# ArduinoClock.net
KiCad netlist of a schematic drawn in EAGLE
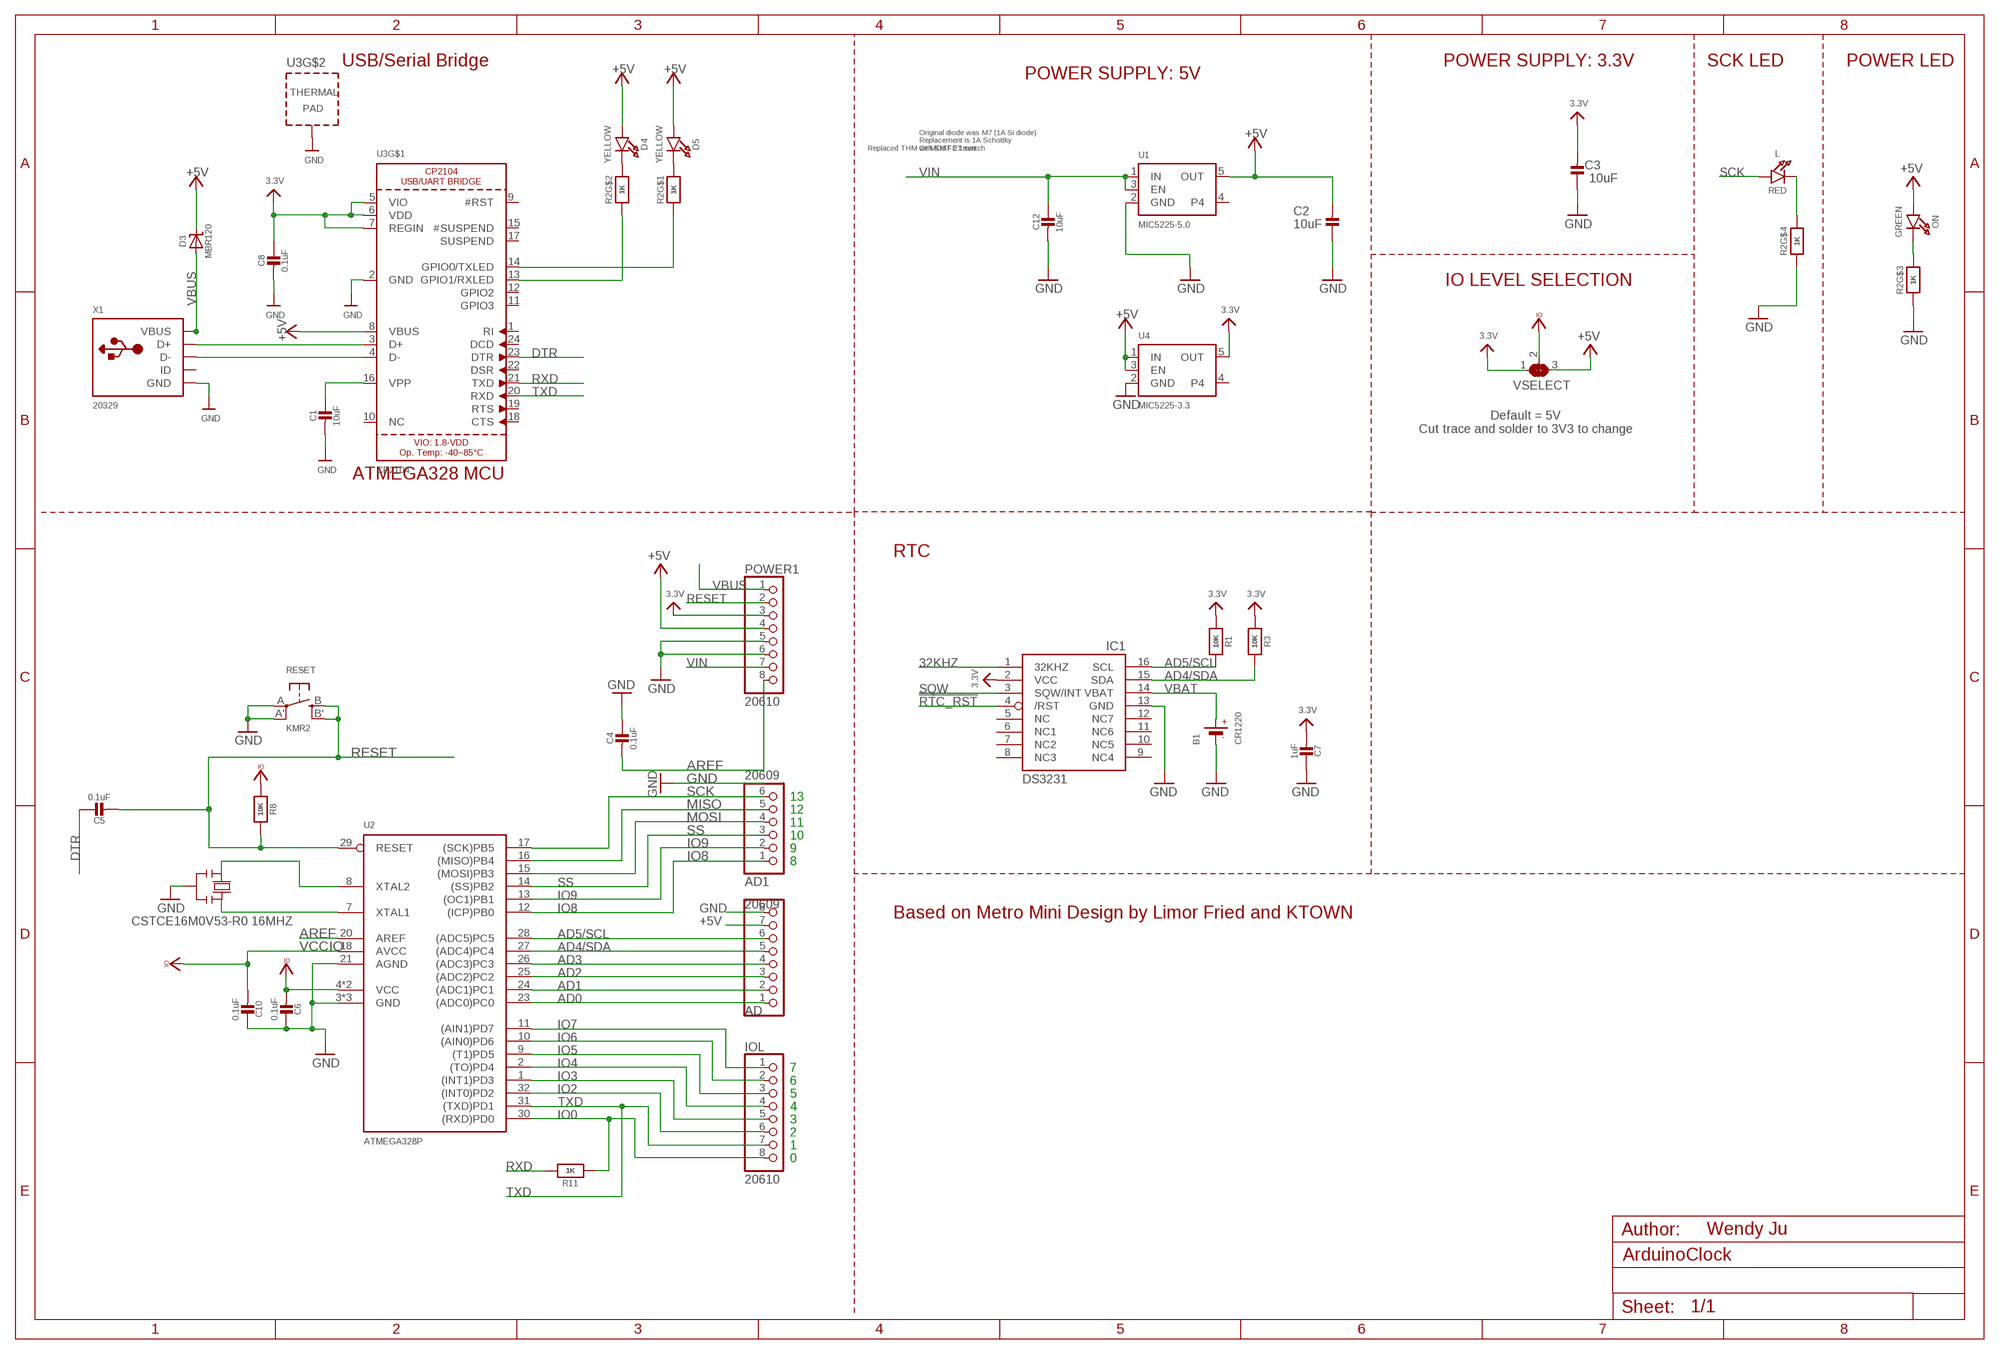
[diagram p0: schematic, sheet 1]

(export (version "E")
  (design (tool "Eeschema 10.0.6"))
  (components
    (comp (ref "AD")
      (value "20609")
      (footprint "eagle-import:1X08_ROUND")
      (libsource (lib "eagle-import") (part "HEADER-1X8ROUND"))
    )
    (comp (ref "AD1")
      (value "20609")
      (footprint "eagle-import:1X06_ROUND")
      (libsource (lib "eagle-import") (part "HEADER-1X6ROUND"))
    )
    (comp (ref "B1")
      (value "CR1220")
      (footprint "eagle-import:CR1220")
      (libsource (lib "eagle-import") (part "BATTERYCR1220_SMT"))
    )
    (comp (ref "C1")
      (value "10uF")
      (footprint "eagle-import:0805-NO")
      (libsource (lib "eagle-import") (part "CAP_CERAMIC0805-NOOUTLINE"))
    )
    (comp (ref "C2")
      (value "10uF")
      (footprint "eagle-import:0805-NO")
      (libsource (lib "eagle-import") (part "CAP_CERAMIC0805-NOOUTLINE"))
    )
    (comp (ref "C3")
      (value "10uF")
      (footprint "eagle-import:0805-NO")
      (libsource (lib "eagle-import") (part "CAP_CERAMIC0805-NOOUTLINE"))
    )
    (comp (ref "C4")
      (value "0.1uF")
      (footprint "eagle-import:0805-NO")
      (libsource (lib "eagle-import") (part "CAP_CERAMIC0805-NOOUTLINE"))
    )
    (comp (ref "C5")
      (value "0.1uF")
      (footprint "eagle-import:_0805MP")
      (libsource (lib "eagle-import") (part "CAP_CERAMIC_0805MP"))
    )
    (comp (ref "C6")
      (value "0.1uF")
      (footprint "eagle-import:0805-NO")
      (libsource (lib "eagle-import") (part "CAP_CERAMIC0805-NOOUTLINE"))
    )
    (comp (ref "C7")
      (value "1uF")
      (footprint "eagle-import:0805-NO")
      (libsource (lib "eagle-import") (part "CAP_CERAMIC0805-NOOUTLINE"))
    )
    (comp (ref "C8")
      (value "0.1uF")
      (footprint "eagle-import:0805-NO")
      (libsource (lib "eagle-import") (part "CAP_CERAMIC0805-NOOUTLINE"))
    )
    (comp (ref "C10")
      (value "0.1uF")
      (footprint "eagle-import:0805-NO")
      (libsource (lib "eagle-import") (part "CAP_CERAMIC0805-NOOUTLINE"))
    )
    (comp (ref "C12")
      (value "10uF")
      (footprint "eagle-import:0805-NO")
      (libsource (lib "eagle-import") (part "CAP_CERAMIC0805-NOOUTLINE"))
    )
    (comp (ref "D3")
      (value "MBR120")
      (footprint "eagle-import:SOD-123")
      (libsource (lib "eagle-import") (part "DIODE-SCHOTTKYSOD-123"))
    )
    (comp (ref "D4")
      (value "YELLOW")
      (footprint "eagle-import:CHIPLED_0805_NOOUTLINE")
      (libsource (lib "eagle-import") (part "LED0805_NOOUTLINE"))
    )
    (comp (ref "D5")
      (value "YELLOW")
      (footprint "eagle-import:CHIPLED_0805_NOOUTLINE")
      (libsource (lib "eagle-import") (part "LED0805_NOOUTLINE"))
    )
    (comp (ref "IC1")
      (value "DS3231/SO")
      (footprint "eagle-import:SO16W")
      (libsource (lib "eagle-import") (part "DS3231/SO"))
    )
    (comp (ref "IOL")
      (value "20610")
      (footprint "eagle-import:1X08_ROUND")
      (libsource (lib "eagle-import") (part "HEADER-1X8ROUND"))
    )
    (comp (ref "L")
      (value "RED")
      (footprint "eagle-import:CHIPLED_0805_NOOUTLINE")
      (libsource (lib "eagle-import") (part "LED0805_NOOUTLINE"))
    )
    (comp (ref "ON")
      (value "GREEN")
      (footprint "eagle-import:CHIPLED_0805_NOOUTLINE")
      (libsource (lib "eagle-import") (part "LED0805_NOOUTLINE"))
    )
    (comp (ref "POWER1")
      (value "20610")
      (footprint "eagle-import:1X08_ROUND_70")
      (libsource (lib "eagle-import") (part "HEADER-1X870MIL"))
    )
    (comp (ref "R1")
      (value "10K")
      (footprint "eagle-import:0805-NO")
      (libsource (lib "eagle-import") (part "RESISTOR0805_NOOUTLINE"))
    )
    (comp (ref "R2")
      (value "1K")
      (footprint "eagle-import:RESPACK_4X0603")
      (libsource (lib "eagle-import") (part "RESISTOR_4PACK"))
    )
    (comp (ref "R3")
      (value "10K")
      (footprint "eagle-import:0805-NO")
      (libsource (lib "eagle-import") (part "RESISTOR0805_NOOUTLINE"))
    )
    (comp (ref "R8")
      (value "10K")
      (footprint "eagle-import:0805-NO")
      (libsource (lib "eagle-import") (part "RESISTOR0805_NOOUTLINE"))
    )
    (comp (ref "R11")
      (value "1K")
      (footprint "eagle-import:0805-NO")
      (libsource (lib "eagle-import") (part "RESISTOR0805_NOOUTLINE"))
    )
    (comp (ref "RESET")
      (value "KMR2")
      (footprint "eagle-import:BTN_KMR2_4.6X2.8")
      (libsource (lib "eagle-import") (part "SWITCH_TACT_SMT4.6X2.8"))
    )
    (comp (ref "U1")
      (value "MIC5225-5.0")
      (footprint "eagle-import:SOT23-5")
      (libsource (lib "eagle-import") (part "VREG_SOT23-5"))
    )
    (comp (ref "U2")
      (value "ATMEGA328P")
      (footprint "eagle-import:MLF32-TH")
      (libsource (lib "eagle-import") (part "ATMEGA328P"))
    )
    (comp (ref "U3")
      (value "CP2104")
      (footprint "eagle-import:QFN24_4MM_SMSC")
      (libsource (lib "eagle-import") (part "CP2104"))
    )
    (comp (ref "U4")
      (value "MIC5225-3.3")
      (footprint "eagle-import:SOT23-5")
      (libsource (lib "eagle-import") (part "VREG_SOT23-5"))
    )
    (comp (ref "VSELECT")
      (value "SOLDERJUMPER_2WAY")
      (footprint "eagle-import:SOLDERJUMPER_2WAY_OPEN_NOPASTE")
      (libsource (lib "eagle-import") (part "SOLDERJUMPER_2WAY"))
    )
    (comp (ref "X1")
      (value "20329")
      (footprint "eagle-import:4UCONN_20329_V2")
      (libsource (lib "eagle-import") (part "USB_MICRO_20329_V2"))
    )
    (comp (ref "Y2")
      (value "CSTCE16M0V53-R0 16MHZ")
      (footprint "eagle-import:RESONATOR")
      (libsource (lib "eagle-import") (part "RESONATORMU"))
    )
  )
  (nets
    (net (code "1") (name "+5V") (class "Default")
      (node (ref "AD") (pin "7") (pinfunction "7_7") (pintype "passive"))
      (node (ref "C2") (pin "2") (pinfunction "2_2") (pintype "passive"))
      (node (ref "D3") (pin "C") (pinfunction "C_C") (pintype "passive"))
      (node (ref "D4") (pin "A") (pinfunction "A_A") (pintype "passive"))
      (node (ref "D5") (pin "A") (pinfunction "A_A") (pintype "passive"))
      (node (ref "ON") (pin "A") (pinfunction "A_A") (pintype "passive"))
      (node (ref "POWER1") (pin "4") (pinfunction "4_4") (pintype "passive"))
      (node (ref "U1") (pin "5") (pinfunction "OUT_5") (pintype "power_in"))
      (node (ref "U3") (pin "8") (pinfunction "VBUS_8") (pintype "power_in"))
      (node (ref "U4") (pin "1") (pinfunction "IN_1") (pintype "power_in"))
      (node (ref "U4") (pin "3") (pinfunction "EN_3") (pintype "input"))
      (node (ref "VSELECT") (pin "3") (pinfunction "3_3") (pintype "passive"))
    )
    (net (code "2") (name "/32KHZ") (class "Default")
      (node (ref "IC1") (pin "1") (pinfunction "32KHZ_1") (pintype "output"))
    )
    (net (code "3") (name "/AD0") (class "Default")
      (node (ref "AD") (pin "1") (pinfunction "1_1") (pintype "passive"))
      (node (ref "U2") (pin "23") (pinfunction "(ADC0)PC0_23") (pintype "bidirectional"))
    )
    (net (code "4") (name "/AD1") (class "Default")
      (node (ref "AD") (pin "2") (pinfunction "2_2") (pintype "passive"))
      (node (ref "U2") (pin "24") (pinfunction "(ADC1)PC1_24") (pintype "bidirectional"))
    )
    (net (code "5") (name "/AD2") (class "Default")
      (node (ref "AD") (pin "3") (pinfunction "3_3") (pintype "passive"))
      (node (ref "U2") (pin "25") (pinfunction "(ADC2)PC2_25") (pintype "bidirectional"))
    )
    (net (code "6") (name "/AD3") (class "Default")
      (node (ref "AD") (pin "4") (pinfunction "4_4") (pintype "passive"))
      (node (ref "U2") (pin "26") (pinfunction "(ADC3)PC3_26") (pintype "bidirectional"))
    )
    (net (code "7") (name "/AD4{slash}SDA") (class "Default")
      (node (ref "AD") (pin "5") (pinfunction "5_5") (pintype "passive"))
      (node (ref "IC1") (pin "15") (pinfunction "SDA_15") (pintype "bidirectional"))
      (node (ref "R3") (pin "2") (pinfunction "2_2") (pintype "passive"))
      (node (ref "U2") (pin "27") (pinfunction "(ADC4)PC4_27") (pintype "bidirectional"))
    )
    (net (code "8") (name "/AD5{slash}SCL") (class "Default")
      (node (ref "AD") (pin "6") (pinfunction "6_6") (pintype "passive"))
      (node (ref "IC1") (pin "16") (pinfunction "SCL_16") (pintype "bidirectional"))
      (node (ref "R1") (pin "2") (pinfunction "2_2") (pintype "passive"))
      (node (ref "U2") (pin "28") (pinfunction "(ADC5)PC5_28") (pintype "bidirectional"))
    )
    (net (code "9") (name "/AREF") (class "Default")
      (node (ref "C4") (pin "2") (pinfunction "2_2") (pintype "passive"))
      (node (ref "POWER1") (pin "8") (pinfunction "8_8") (pintype "passive"))
      (node (ref "U2") (pin "20") (pinfunction "AREF_20") (pintype "power_in"))
    )
    (net (code "10") (name "/DTR") (class "Default")
      (node (ref "C5") (pin "1") (pinfunction "1_1") (pintype "passive"))
      (node (ref "U3") (pin "23") (pinfunction "DTR_23") (pintype "output"))
    )
    (net (code "11") (name "/IO0") (class "Default")
      (node (ref "IOL") (pin "8") (pinfunction "8_8") (pintype "passive"))
      (node (ref "R11") (pin "1") (pinfunction "1_1") (pintype "passive"))
      (node (ref "U2") (pin "30") (pinfunction "(RXD)PD0_30") (pintype "bidirectional"))
    )
    (net (code "12") (name "/IO2") (class "Default")
      (node (ref "IOL") (pin "6") (pinfunction "6_6") (pintype "passive"))
      (node (ref "U2") (pin "32") (pinfunction "(INT0)PD2_32") (pintype "bidirectional"))
    )
    (net (code "13") (name "/IO3") (class "Default")
      (node (ref "IOL") (pin "5") (pinfunction "5_5") (pintype "passive"))
      (node (ref "U2") (pin "1") (pinfunction "(INT1)PD3_1") (pintype "bidirectional"))
    )
    (net (code "14") (name "/IO4") (class "Default")
      (node (ref "IOL") (pin "4") (pinfunction "4_4") (pintype "passive"))
      (node (ref "U2") (pin "2") (pinfunction "(TO)PD4_2") (pintype "bidirectional"))
    )
    (net (code "15") (name "/IO5") (class "Default")
      (node (ref "IOL") (pin "3") (pinfunction "3_3") (pintype "passive"))
      (node (ref "U2") (pin "9") (pinfunction "(T1)PD5_9") (pintype "bidirectional"))
    )
    (net (code "16") (name "/IO6") (class "Default")
      (node (ref "IOL") (pin "2") (pinfunction "2_2") (pintype "passive"))
      (node (ref "U2") (pin "10") (pinfunction "(AIN0)PD6_10") (pintype "bidirectional"))
    )
    (net (code "17") (name "/IO7") (class "Default")
      (node (ref "IOL") (pin "1") (pinfunction "1_1") (pintype "passive"))
      (node (ref "U2") (pin "11") (pinfunction "(AIN1)PD7_11") (pintype "bidirectional"))
    )
    (net (code "18") (name "/IO8") (class "Default")
      (node (ref "AD1") (pin "1") (pinfunction "1_1") (pintype "passive"))
      (node (ref "U2") (pin "12") (pinfunction "(ICP)PB0_12") (pintype "bidirectional"))
    )
    (net (code "19") (name "/IO9") (class "Default")
      (node (ref "AD1") (pin "2") (pinfunction "2_2") (pintype "passive"))
      (node (ref "U2") (pin "13") (pinfunction "(OC1)PB1_13") (pintype "bidirectional"))
    )
    (net (code "20") (name "/MISO") (class "Default")
      (node (ref "AD1") (pin "5") (pinfunction "5_5") (pintype "passive"))
      (node (ref "U2") (pin "16") (pinfunction "(MISO)PB4_16") (pintype "bidirectional"))
    )
    (net (code "21") (name "/MOSI") (class "Default")
      (node (ref "AD1") (pin "4") (pinfunction "4_4") (pintype "passive"))
      (node (ref "U2") (pin "15") (pinfunction "(MOSI)PB3_15") (pintype "bidirectional"))
    )
    (net (code "22") (name "/RESET") (class "Default")
      (node (ref "C5") (pin "2") (pinfunction "2_2") (pintype "passive"))
      (node (ref "POWER1") (pin "2") (pinfunction "2_2") (pintype "passive"))
      (node (ref "R8") (pin "1") (pinfunction "1_1") (pintype "passive"))
      (node (ref "RESET") (pin "B") (pinfunction "S_B") (pintype "passive"))
      (node (ref "RESET") (pin "B'") (pinfunction "S1_B'") (pintype "passive"))
      (node (ref "U2") (pin "29") (pinfunction "RESET_29") (pintype "bidirectional"))
    )
    (net (code "23") (name "/RXD") (class "Default")
      (node (ref "R11") (pin "2") (pinfunction "2_2") (pintype "passive"))
      (node (ref "U3") (pin "21") (pinfunction "TXD_21") (pintype "output"))
    )
    (net (code "24") (name "/SCK") (class "Default")
      (node (ref "AD1") (pin "6") (pinfunction "6_6") (pintype "passive"))
      (node (ref "L") (pin "A") (pinfunction "A_A") (pintype "passive"))
      (node (ref "U2") (pin "17") (pinfunction "(SCK)PB5_17") (pintype "bidirectional"))
    )
    (net (code "25") (name "/SQW") (class "Default")
      (node (ref "IC1") (pin "3") (pinfunction "SQW/INT_3") (pintype "output"))
    )
    (net (code "26") (name "/SS") (class "Default")
      (node (ref "AD1") (pin "3") (pinfunction "3_3") (pintype "passive"))
      (node (ref "U2") (pin "14") (pinfunction "(SS)PB2_14") (pintype "bidirectional"))
    )
    (net (code "27") (name "/TXD") (class "Default")
      (node (ref "IOL") (pin "7") (pinfunction "7_7") (pintype "passive"))
      (node (ref "U2") (pin "31") (pinfunction "(TXD)PD1_31") (pintype "bidirectional"))
      (node (ref "U3") (pin "20") (pinfunction "RXD_20") (pintype "input"))
    )
    (net (code "28") (name "/VBAT") (class "Default")
      (node (ref "B1") (pin "+$1") (pinfunction "+_+$1") (pintype "passive"))
      (node (ref "IC1") (pin "14") (pinfunction "VBAT_14") (pintype "power_in"))
    )
    (net (code "29") (name "/VBUS") (class "Default")
      (node (ref "D3") (pin "A") (pinfunction "A_A") (pintype "passive"))
      (node (ref "POWER1") (pin "1") (pinfunction "1_1") (pintype "passive"))
      (node (ref "X1") (pin "VBUS") (pinfunction "VBUS_VBUS") (pintype "power_in"))
    )
    (net (code "30") (name "/VIN") (class "Default")
      (node (ref "C12") (pin "1") (pinfunction "1_1") (pintype "passive"))
      (node (ref "POWER1") (pin "7") (pinfunction "7_7") (pintype "passive"))
      (node (ref "U1") (pin "1") (pinfunction "IN_1") (pintype "power_in"))
      (node (ref "U1") (pin "3") (pinfunction "EN_3") (pintype "input"))
    )
    (net (code "31") (name "/~{RTC_RST}") (class "Default")
      (node (ref "IC1") (pin "4") (pinfunction "/RST_4") (pintype "passive"))
    )
    (net (code "32") (name "3.3V") (class "Default")
      (node (ref "C3") (pin "2") (pinfunction "2_2") (pintype "passive"))
      (node (ref "C7") (pin "2") (pinfunction "2_2") (pintype "passive"))
      (node (ref "C8") (pin "1") (pinfunction "1_1") (pintype "passive"))
      (node (ref "IC1") (pin "2") (pinfunction "VCC_2") (pintype "power_in"))
      (node (ref "POWER1") (pin "3") (pinfunction "3_3") (pintype "passive"))
      (node (ref "R1") (pin "1") (pinfunction "1_1") (pintype "passive"))
      (node (ref "R3") (pin "1") (pinfunction "1_1") (pintype "passive"))
      (node (ref "U3") (pin "5") (pinfunction "VIO_5") (pintype "power_in"))
      (node (ref "U3") (pin "6") (pinfunction "VDD_6") (pintype "power_in"))
      (node (ref "U3") (pin "7") (pinfunction "REGIN_7") (pintype "power_in"))
      (node (ref "U4") (pin "5") (pinfunction "OUT_5") (pintype "power_in"))
      (node (ref "VSELECT") (pin "1") (pinfunction "1_1") (pintype "passive"))
    )
    (net (code "33") (name "GND") (class "Default")
      (node (ref "AD") (pin "8") (pinfunction "8_8") (pintype "passive"))
      (node (ref "B1") (pin "-") (pinfunction "-_-") (pintype "passive"))
      (node (ref "C1") (pin "2") (pinfunction "2_2") (pintype "passive"))
      (node (ref "C10") (pin "1") (pinfunction "1_1") (pintype "passive"))
      (node (ref "C12") (pin "2") (pinfunction "2_2") (pintype "passive"))
      (node (ref "C2") (pin "1") (pinfunction "1_1") (pintype "passive"))
      (node (ref "C3") (pin "1") (pinfunction "1_1") (pintype "passive"))
      (node (ref "C4") (pin "1") (pinfunction "1_1") (pintype "passive"))
      (node (ref "C6") (pin "1") (pinfunction "1_1") (pintype "passive"))
      (node (ref "C7") (pin "1") (pinfunction "1_1") (pintype "passive"))
      (node (ref "C8") (pin "2") (pinfunction "2_2") (pintype "passive"))
      (node (ref "IC1") (pin "13") (pinfunction "GND_13") (pintype "power_in"))
      (node (ref "POWER1") (pin "5") (pinfunction "5_5") (pintype "passive"))
      (node (ref "POWER1") (pin "6") (pinfunction "6_6") (pintype "passive"))
      (node (ref "R2") (pin "3") (pinfunction "1_3") (pintype "passive"))
      (node (ref "R2") (pin "4") (pinfunction "1_4") (pintype "passive"))
      (node (ref "RESET") (pin "A") (pinfunction "P_A") (pintype "passive"))
      (node (ref "RESET") (pin "A'") (pinfunction "P1_A'") (pintype "passive"))
      (node (ref "U1") (pin "2") (pinfunction "GND_2") (pintype "power_in"))
      (node (ref "U2") (pin "21") (pinfunction "AGND_21") (pintype "power_in"))
      (node (ref "U2") (pin "3") (pinfunction "GND_3") (pintype "power_in"))
      (node (ref "U2") (pin "5") (pinfunction "GND_5") (pintype "power_in"))
      (node (ref "U2") (pin "TH") (pinfunction "GND_TH") (pintype "power_in"))
      (node (ref "U3") (pin "2") (pinfunction "GND_2") (pintype "power_in"))
      (node (ref "U3") (pin "THERM") (pinfunction "TP_THERM") (pintype "power_in"))
      (node (ref "U4") (pin "2") (pinfunction "GND_2") (pintype "power_in"))
      (node (ref "X1") (pin "BASE@1") (pinfunction "GND_BASE@1") (pintype "power_in"))
      (node (ref "X1") (pin "BASE@2") (pinfunction "GND_BASE@2") (pintype "power_in"))
      (node (ref "X1") (pin "GND") (pinfunction "GND_GND") (pintype "power_in"))
      (node (ref "X1") (pin "SPRT@1") (pinfunction "GND_SPRT@1") (pintype "power_in"))
      (node (ref "X1") (pin "SPRT@2") (pinfunction "GND_SPRT@2") (pintype "power_in"))
      (node (ref "X1") (pin "SPRT@3") (pinfunction "GND_SPRT@3") (pintype "power_in"))
      (node (ref "X1") (pin "SPRT@4") (pinfunction "GND_SPRT@4") (pintype "power_in"))
      (node (ref "Y2") (pin "2") (pinfunction "2_2") (pintype "passive"))
    )
    (net (code "34") (name "Net-(R2A-2)") (class "Default")
      (node (ref "D5") (pin "C") (pinfunction "C_C") (pintype "passive"))
      (node (ref "R2") (pin "8") (pinfunction "2_8") (pintype "passive"))
    )
    (net (code "35") (name "Net-(R2B-1)") (class "Default")
      (node (ref "R2") (pin "2") (pinfunction "1_2") (pintype "passive"))
      (node (ref "U3") (pin "13") (pinfunction "GPIO1/RXLED_13") (pintype "bidirectional"))
    )
    (net (code "36") (name "Net-(R2B-2)") (class "Default")
      (node (ref "D4") (pin "C") (pinfunction "C_C") (pintype "passive"))
      (node (ref "R2") (pin "7") (pinfunction "2_7") (pintype "passive"))
    )
    (net (code "37") (name "Net-(R2C-2)") (class "Default")
      (node (ref "ON") (pin "C") (pinfunction "C_C") (pintype "passive"))
      (node (ref "R2") (pin "6") (pinfunction "2_6") (pintype "passive"))
    )
    (net (code "38") (name "Net-(R2D-2)") (class "Default")
      (node (ref "L") (pin "C") (pinfunction "C_C") (pintype "passive"))
      (node (ref "R2") (pin "5") (pinfunction "2_5") (pintype "passive"))
    )
    (net (code "39") (name "Net-(U2-XTAL1)") (class "Default")
      (node (ref "U2") (pin "7") (pinfunction "XTAL1_7") (pintype "bidirectional"))
      (node (ref "Y2") (pin "3") (pinfunction "3_3") (pintype "passive"))
    )
    (net (code "40") (name "Net-(U2-XTAL2)") (class "Default")
      (node (ref "U2") (pin "8") (pinfunction "XTAL2_8") (pintype "bidirectional"))
      (node (ref "Y2") (pin "1") (pinfunction "1_1") (pintype "passive"))
    )
    (net (code "41") (name "Net-(U3A-D+)") (class "Default")
      (node (ref "U3") (pin "3") (pinfunction "D+_3") (pintype "bidirectional"))
      (node (ref "X1") (pin "D+") (pinfunction "D+_D+") (pintype "bidirectional"))
    )
    (net (code "42") (name "Net-(U3A-D-)") (class "Default")
      (node (ref "U3") (pin "4") (pinfunction "D-_4") (pintype "bidirectional"))
      (node (ref "X1") (pin "D-") (pinfunction "D-_D-") (pintype "bidirectional"))
    )
    (net (code "43") (name "Net-(U3A-GPIO0{slash}TXLED)") (class "Default")
      (node (ref "R2") (pin "1") (pinfunction "1_1") (pintype "passive"))
      (node (ref "U3") (pin "14") (pinfunction "GPIO0/TXLED_14") (pintype "bidirectional"))
    )
    (net (code "44") (name "Net-(U3A-VPP)") (class "Default")
      (node (ref "C1") (pin "1") (pinfunction "1_1") (pintype "passive"))
      (node (ref "U3") (pin "16") (pinfunction "VPP_16") (pintype "bidirectional"))
    )
    (net (code "45") (name "VCCIO") (class "Default")
      (node (ref "C10") (pin "2") (pinfunction "2_2") (pintype "passive"))
      (node (ref "C6") (pin "2") (pinfunction "2_2") (pintype "passive"))
      (node (ref "R8") (pin "2") (pinfunction "2_2") (pintype "passive"))
      (node (ref "U2") (pin "18") (pinfunction "AVCC_18") (pintype "power_in"))
      (node (ref "U2") (pin "4") (pinfunction "VCC_4") (pintype "power_in"))
      (node (ref "U2") (pin "6") (pinfunction "VCC_6") (pintype "power_in"))
      (node (ref "VSELECT") (pin "2") (pinfunction "2_2") (pintype "passive"))
    )
    (net (code "46") (name "unconnected-(IC1-NC-Pad5)") (class "Default")
      (node (ref "IC1") (pin "5") (pinfunction "NC_5") (pintype "no_connect"))
    )
    (net (code "47") (name "unconnected-(IC1-NC1-Pad6)") (class "Default")
      (node (ref "IC1") (pin "6") (pinfunction "NC1_6") (pintype "no_connect"))
    )
    (net (code "48") (name "unconnected-(IC1-NC2-Pad7)") (class "Default")
      (node (ref "IC1") (pin "7") (pinfunction "NC2_7") (pintype "no_connect"))
    )
    (net (code "49") (name "unconnected-(IC1-NC3-Pad8)") (class "Default")
      (node (ref "IC1") (pin "8") (pinfunction "NC3_8") (pintype "no_connect"))
    )
    (net (code "50") (name "unconnected-(IC1-NC4-Pad9)") (class "Default")
      (node (ref "IC1") (pin "9") (pinfunction "NC4_9") (pintype "no_connect"))
    )
    (net (code "51") (name "unconnected-(IC1-NC5-Pad10)") (class "Default")
      (node (ref "IC1") (pin "10") (pinfunction "NC5_10") (pintype "no_connect"))
    )
    (net (code "52") (name "unconnected-(IC1-NC6-Pad11)") (class "Default")
      (node (ref "IC1") (pin "11") (pinfunction "NC6_11") (pintype "no_connect"))
    )
    (net (code "53") (name "unconnected-(IC1-NC7-Pad12)") (class "Default")
      (node (ref "IC1") (pin "12") (pinfunction "NC7_12") (pintype "no_connect"))
    )
    (net (code "54") (name "unconnected-(U1-P4-Pad4)") (class "Default")
      (node (ref "U1") (pin "4") (pinfunction "P4_4") (pintype "bidirectional"))
    )
    (net (code "55") (name "unconnected-(U3A-#RST-Pad9)") (class "Default")
      (node (ref "U3") (pin "9") (pinfunction "#RST_9") (pintype "bidirectional"))
    )
    (net (code "56") (name "unconnected-(U3A-#SUSPEND-Pad15)") (class "Default")
      (node (ref "U3") (pin "15") (pinfunction "#SUSPEND_15") (pintype "output"))
    )
    (net (code "57") (name "unconnected-(U3A-CTS-Pad18)") (class "Default")
      (node (ref "U3") (pin "18") (pinfunction "CTS_18") (pintype "input"))
    )
    (net (code "58") (name "unconnected-(U3A-DCD-Pad24)") (class "Default")
      (node (ref "U3") (pin "24") (pinfunction "DCD_24") (pintype "input"))
    )
    (net (code "59") (name "unconnected-(U3A-DSR-Pad22)") (class "Default")
      (node (ref "U3") (pin "22") (pinfunction "DSR_22") (pintype "input"))
    )
    (net (code "60") (name "unconnected-(U3A-GPIO2-Pad12)") (class "Default")
      (node (ref "U3") (pin "12") (pinfunction "GPIO2_12") (pintype "bidirectional"))
    )
    (net (code "61") (name "unconnected-(U3A-GPIO3-Pad11)") (class "Default")
      (node (ref "U3") (pin "11") (pinfunction "GPIO3_11") (pintype "bidirectional"))
    )
    (net (code "62") (name "unconnected-(U3A-NC-Pad10)") (class "Default")
      (node (ref "U3") (pin "10") (pinfunction "NC_10") (pintype "no_connect"))
    )
    (net (code "63") (name "unconnected-(U3A-RI-Pad1)") (class "Default")
      (node (ref "U3") (pin "1") (pinfunction "RI_1") (pintype "input"))
    )
    (net (code "64") (name "unconnected-(U3A-RTS-Pad19)") (class "Default")
      (node (ref "U3") (pin "19") (pinfunction "RTS_19") (pintype "output"))
    )
    (net (code "65") (name "unconnected-(U3A-SUSPEND-Pad17)") (class "Default")
      (node (ref "U3") (pin "17") (pinfunction "SUSPEND_17") (pintype "output"))
    )
    (net (code "66") (name "unconnected-(U4-P4-Pad4)") (class "Default")
      (node (ref "U4") (pin "4") (pinfunction "P4_4") (pintype "bidirectional"))
    )
    (net (code "67") (name "unconnected-(X1-PadID)") (class "Default")
      (node (ref "X1") (pin "ID") (pinfunction "ID_ID") (pintype "bidirectional"))
    )
  )
)
